# ProDoc.net
KiCad netlist of a schematic drawn in EasyEDA Pro
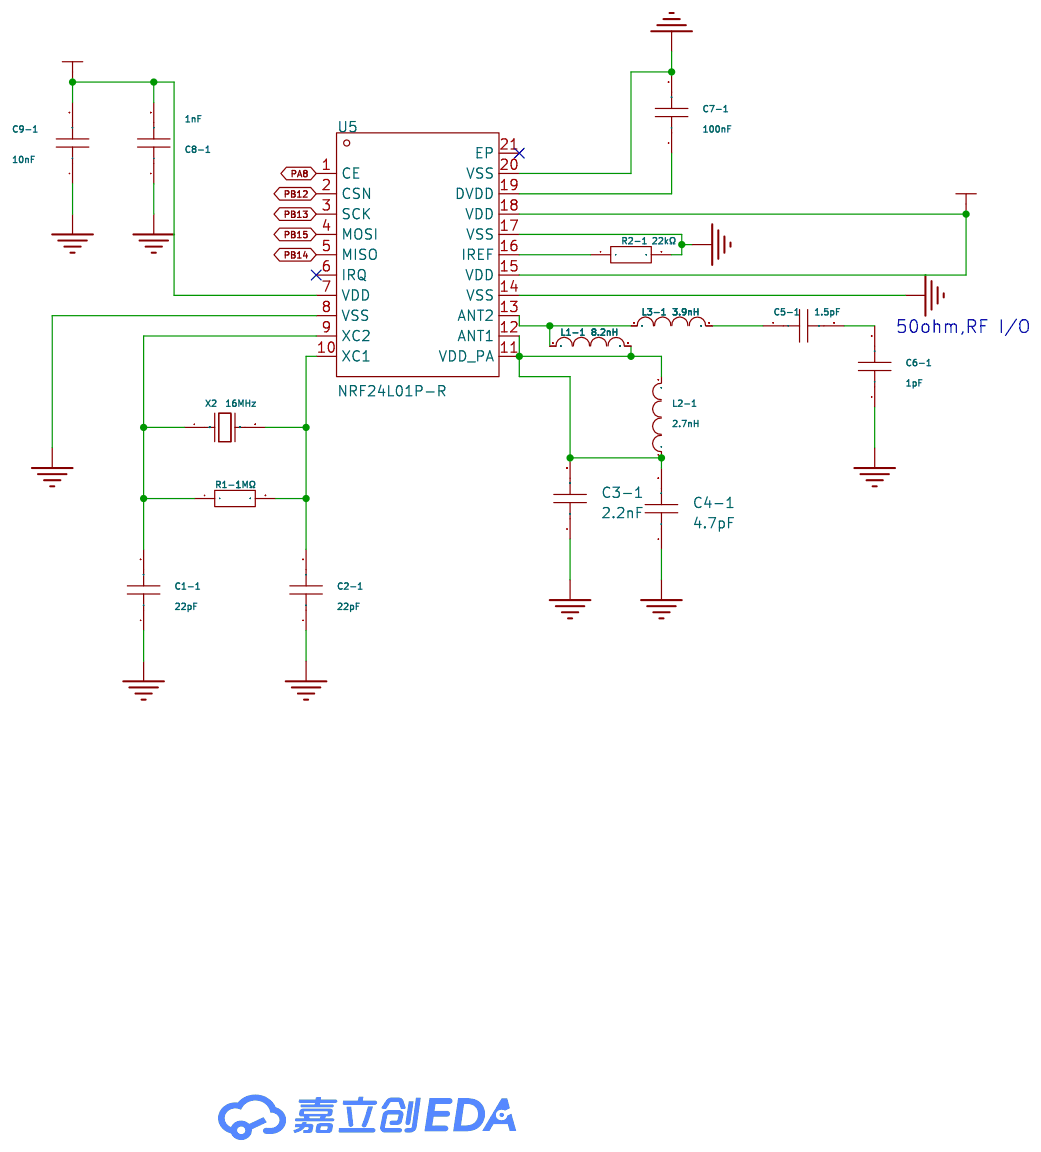
[diagram p0: P2]
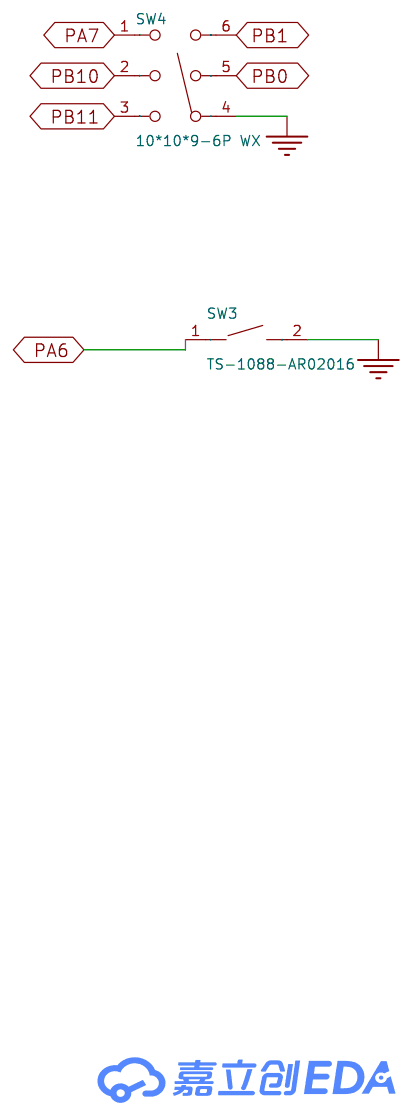
[diagram p1: P3]
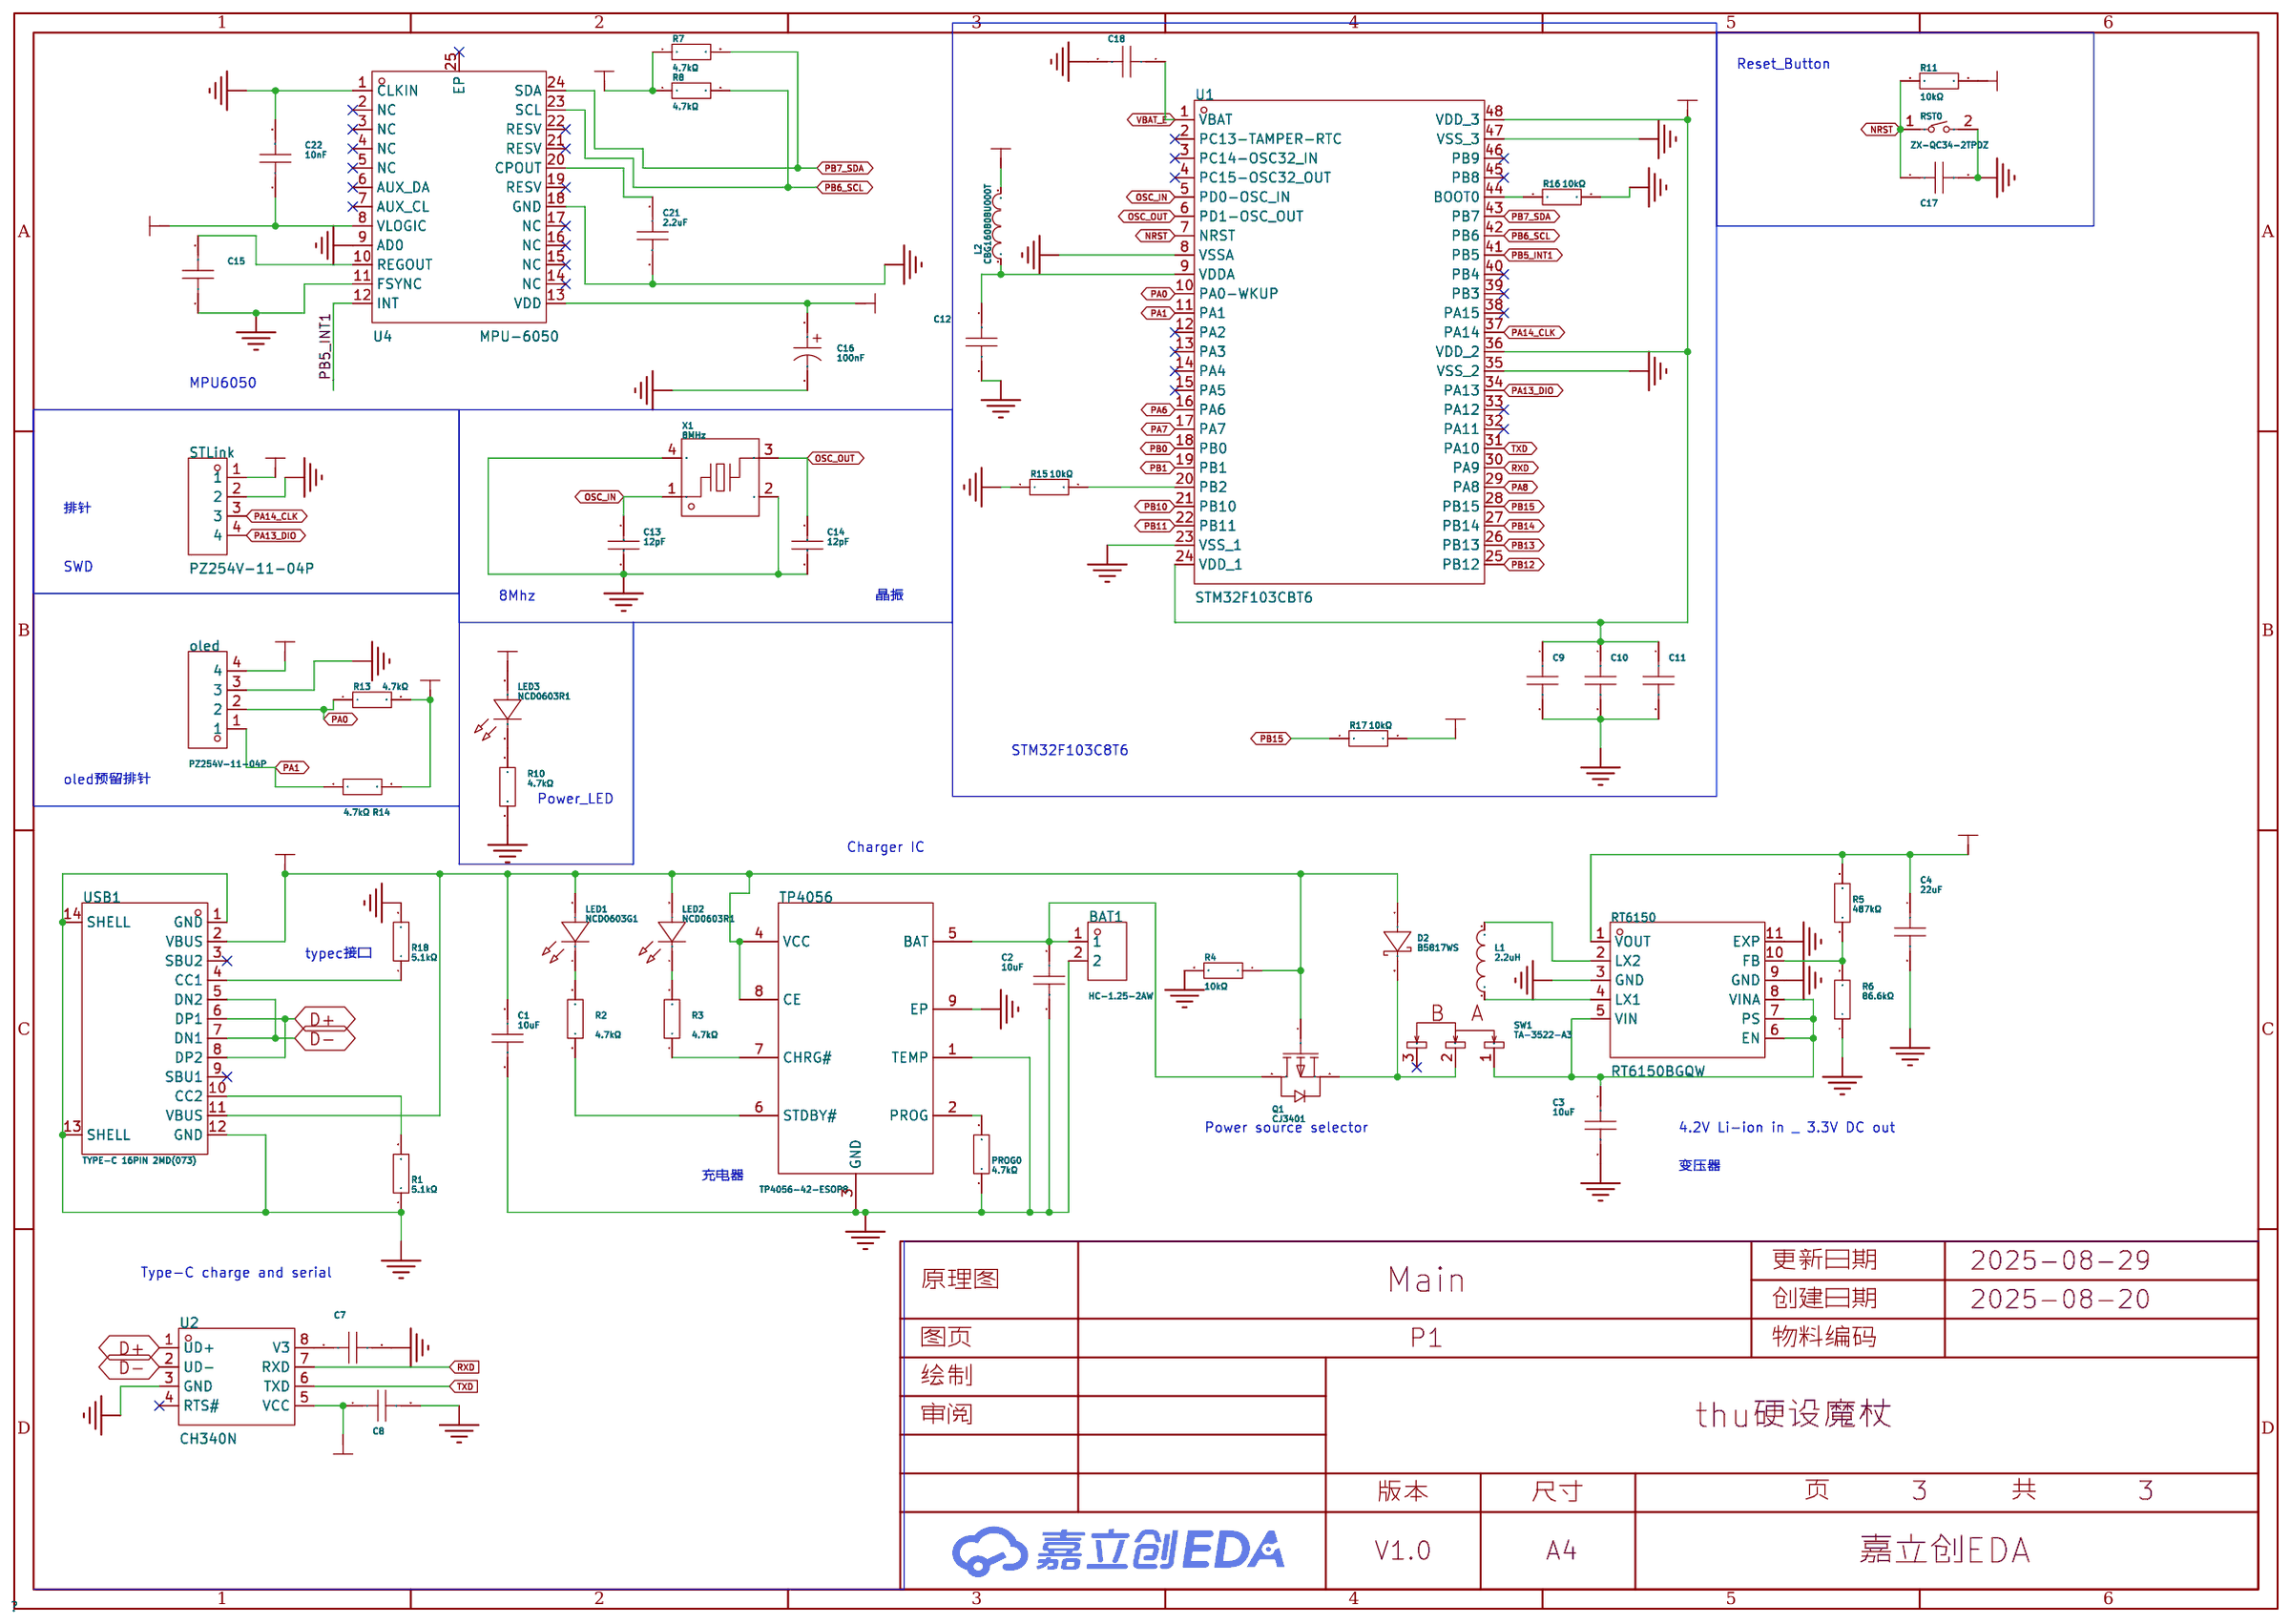
[diagram p2: P1]

(export (version "E")
  (design (tool "Eeschema 10.0.6"))
  (components
    (comp (ref "C1-1")
      (value "22pF")
      (fields
        (field (name "Manufacturer Part") "CL10C220JB8NNNC")
        (field (name "Manufacturer") "SAMSUNG(三星)")
      )
      (libsource (lib "easyedapro") (part "Capacitance"))
    )
    (comp (ref "C2-1")
      (value "22pF")
      (fields
        (field (name "Manufacturer Part") "CL10C220JB8NNNC")
        (field (name "Manufacturer") "SAMSUNG(三星)")
      )
      (libsource (lib "easyedapro") (part "Capacitance"))
    )
    (comp (ref "C3-1")
      (value "2.2nF")
      (fields
        (field (name "Manufacturer Part") "FCC0603B222K500CT")
        (field (name "Manufacturer") "FOJAN(富捷)")
      )
      (libsource (lib "easyedapro") (part "Capacitance"))
    )
    (comp (ref "C4-1")
      (value "4.7pF")
      (fields (field (name "Manufacturer Part") "0603CG4R7C500NT") (field (name "Manufacturer") "FH(风华)"))
      (libsource (lib "easyedapro") (part "Capacitance"))
    )
    (comp (ref "C5-1")
      (value "1.5pF")
      (fields (field (name "Manufacturer Part") "0603CG1R5C500NT") (field (name "Manufacturer") "FH(风华)"))
      (libsource (lib "easyedapro") (part "Capacitance"))
    )
    (comp (ref "C6-1")
      (value "1pF")
      (fields (field (name "Manufacturer Part") "0603CG1R0C500NT") (field (name "Manufacturer") "FH(风华)"))
      (libsource (lib "easyedapro") (part "Capacitance"))
    )
    (comp (ref "C7-1")
      (value "100nF")
      (fields
        (field (name "Manufacturer Part") "CGA0603X7R104K500JT")
        (field (name "Manufacturer") "HRE(芯声)")
      )
      (libsource (lib "easyedapro") (part "Capacitance"))
    )
    (comp (ref "C8-1")
      (value "1nF")
      (fields
        (field (name "Manufacturer Part") "CL10B102KB8NNNC")
        (field (name "Manufacturer") "SAMSUNG(三星)")
      )
      (libsource (lib "easyedapro") (part "Capacitance"))
    )
    (comp (ref "C9-1")
      (value "10nF")
      (fields (field (name "Manufacturer Part") "0603B103K500NT") (field (name "Manufacturer") "FH(风华)"))
      (libsource (lib "easyedapro") (part "Capacitance"))
    )
    (comp (ref "L1-1")
      (value "8.2nH")
      (fields (field (name "Manufacturer Part") "LQG18HN8N2J00D") (field (name "Manufacturer") "muRata(村田)"))
      (libsource (lib "easyedapro") (part "SDFL1608S100KTF"))
    )
    (comp (ref "L2-1")
      (value "2.7nH")
      (fields
        (field (name "Manufacturer Part") "SCC1608C2N7SSP")
        (field (name "Manufacturer") "Sunltech(顺磁)")
      )
      (libsource (lib "easyedapro") (part "SDFL1608S100KTF"))
    )
    (comp (ref "L3-1")
      (value "3.9nH")
      (fields
        (field (name "Manufacturer Part") "SDCL1608C3N9STDF")
        (field (name "Manufacturer") "Sunlord(顺络)")
      )
      (libsource (lib "easyedapro") (part "SDFL1608S100KTF"))
    )
    (comp (ref "R1-1")
      (value "1MΩ")
      (fields
        (field (name "Manufacturer Part") "0603WAF1004T5E")
        (field (name "Manufacturer") "UNI-ROYAL(厚声)")
      )
      (libsource (lib "easyedapro") (part "电阻"))
    )
    (comp (ref "R2-1")
      (value "22kΩ")
      (fields
        (field (name "Manufacturer Part") "0603WAF2202T5E")
        (field (name "Manufacturer") "UNI-ROYAL(厚声)")
      )
      (libsource (lib "easyedapro") (part "电阻"))
    )
    (comp (ref "U5")
      (value "NRF24L01P-R")
      (fields (field (name "Manufacturer") "NORDIC"))
      (libsource (lib "easyedapro") (part "NRF24L01_C1558392"))
    )
    (comp (ref "X2")
      (value "16MHz")
      (fields (field (name "Manufacturer Part") "X49SD16MSD2SC") (field (name "Manufacturer") "YXC(扬兴晶振)"))
      (libsource (lib "easyedapro") (part "SCBYS16X00000ELRJ"))
    )
    (comp (ref "SW3")
      (value "TS-1088-AR02016")
      (footprint "easyedapro:SW-SMD_L3.9-W3.0-P4.45")
      (fields (field (name "Manufacturer") "XUNPU(讯普)"))
      (libsource (lib "easyedapro") (part "TS-1088-AR02016"))
    )
    (comp (ref "SW4")
      (value "10*10*9-6P WX")
      (footprint "easyedapro:SW-SMD-6P-L10.5-W10.0_C2858290")
      (fields (field (name "Manufacturer") "SHOU HAN(首韩)"))
      (libsource (lib "easyedapro") (part "10*10*9-6P WX"))
    )
    (comp (ref "BAT1")
      (value "HC-1.25-2AW")
      (footprint "easyedapro:CONN-TH_2P-P1.25_HCTL_HC-1.25-2AW")
      (fields (field (name "Manufacturer") "HCTL(华灿天禄)"))
      (libsource (lib "easyedapro") (part "HC-1.25-2AW"))
    )
    (comp (ref "C1")
      (value "10uF")
      (fields
        (field (name "Manufacturer Part") "CL10A106KP8NNNC")
        (field (name "Manufacturer") "SAMSUNG(三星)")
      )
      (libsource (lib "easyedapro") (part "CC0603JRNPO9BN101"))
    )
    (comp (ref "C2")
      (value "10uF")
      (fields
        (field (name "Manufacturer Part") "CL10A106KP8NNNC")
        (field (name "Manufacturer") "SAMSUNG(三星)")
      )
      (libsource (lib "easyedapro") (part "CC0603JRNPO9BN101"))
    )
    (comp (ref "C3")
      (value "10uF")
      (fields
        (field (name "Manufacturer Part") "CL10A106KP8NNNC")
        (field (name "Manufacturer") "SAMSUNG(三星)")
      )
      (libsource (lib "easyedapro") (part "CC0603JRNPO9BN101"))
    )
    (comp (ref "C4")
      (value "22uF")
      (fields
        (field (name "Manufacturer Part") "CL10A226MO7JZNC")
        (field (name "Manufacturer") "SAMSUNG(三星)")
      )
      (libsource (lib "easyedapro") (part "CC0603JRNPO9BN101"))
    )
    (comp (ref "C7")
      (value "100nF")
      (fields
        (field (name "Manufacturer Part") "CT41G-0603-2X1-50V-0.1μF-K(N)")
        (field (name "Manufacturer") "TORCH(火炬)")
      )
      (libsource (lib "easyedapro") (part "CC0603JRNPO9BN101"))
    )
    (comp (ref "C8")
      (value "100nF")
      (fields
        (field (name "Manufacturer Part") "CT41G-0603-2X1-50V-0.1μF-K(N)")
        (field (name "Manufacturer") "TORCH(火炬)")
      )
      (libsource (lib "easyedapro") (part "CC0603JRNPO9BN101"))
    )
    (comp (ref "C9")
      (value "100nF")
      (fields
        (field (name "Manufacturer Part") "CT41G-0603-2X1-50V-0.1μF-K(N)")
        (field (name "Manufacturer") "TORCH(火炬)")
      )
      (libsource (lib "easyedapro") (part "CC0603JRNPO9BN101"))
    )
    (comp (ref "C10")
      (value "100nF")
      (fields
        (field (name "Manufacturer Part") "CT41G-0603-2X1-50V-0.1μF-K(N)")
        (field (name "Manufacturer") "TORCH(火炬)")
      )
      (libsource (lib "easyedapro") (part "CC0603JRNPO9BN101"))
    )
    (comp (ref "C11")
      (value "100nF")
      (fields
        (field (name "Manufacturer Part") "CT41G-0603-2X1-50V-0.1μF-K(N)")
        (field (name "Manufacturer") "TORCH(火炬)")
      )
      (libsource (lib "easyedapro") (part "CC0603JRNPO9BN101"))
    )
    (comp (ref "C12")
      (value "100nF")
      (fields
        (field (name "Manufacturer Part") "CT41G-0603-2X1-50V-0.1μF-K(N)")
        (field (name "Manufacturer") "TORCH(火炬)")
      )
      (libsource (lib "easyedapro") (part "CC0603JRNPO9BN101"))
    )
    (comp (ref "C13")
      (value "12pF")
      (fields
        (field (name "Manufacturer Part") "CL10C120JB8NNNC")
        (field (name "Manufacturer") "SAMSUNG(三星)")
      )
      (libsource (lib "easyedapro") (part "CC0603JRNPO9BN200"))
    )
    (comp (ref "C14")
      (value "12pF")
      (fields
        (field (name "Manufacturer Part") "CL10C120JB8NNNC")
        (field (name "Manufacturer") "SAMSUNG(三星)")
      )
      (libsource (lib "easyedapro") (part "CC0603JRNPO9BN200"))
    )
    (comp (ref "C15")
      (value "100nF")
      (fields
        (field (name "Manufacturer Part") "CT41G-0603-2X1-50V-0.1μF-K(N)")
        (field (name "Manufacturer") "TORCH(火炬)")
      )
      (libsource (lib "easyedapro") (part "CC0603JRNPO9BN101"))
    )
    (comp (ref "C16")
      (value "100nF")
      (fields
        (field (name "Manufacturer Part") "CGA0603X7R104K500JT")
        (field (name "Manufacturer") "HRE(芯声)")
      )
      (libsource (lib "easyedapro") (part "CA45-A-35V-0.1UF-K"))
    )
    (comp (ref "C17")
      (value "100nF")
      (fields
        (field (name "Manufacturer Part") "CT41G-0603-2X1-50V-0.1μF-K(N)")
        (field (name "Manufacturer") "TORCH(火炬)")
      )
      (libsource (lib "easyedapro") (part "CC0603JRNPO9BN101"))
    )
    (comp (ref "C18")
      (value "100nF")
      (fields
        (field (name "Manufacturer Part") "CT41G-0603-2X1-50V-0.1μF-K(N)")
        (field (name "Manufacturer") "TORCH(火炬)")
      )
      (libsource (lib "easyedapro") (part "CC0603JRNPO9BN101"))
    )
    (comp (ref "C21")
      (value "2.2uF")
      (fields
        (field (name "Manufacturer Part") "CL10A225KO8NNNC")
        (field (name "Manufacturer") "SAMSUNG(三星)")
      )
      (libsource (lib "easyedapro") (part "CC0603JRNPO9BN101"))
    )
    (comp (ref "C22")
      (value "10nF")
      (fields
        (field (name "Manufacturer Part") "CC0603KRX7R9BB103")
        (field (name "Manufacturer") "YAGEO(国巨)")
      )
      (libsource (lib "easyedapro") (part "CC0603JRNPO9BN101"))
    )
    (comp (ref "D2")
      (value "B5817WS")
      (footprint "easyedapro:SOD-323_L1.7-W1.3-LS2.5-FD")
      (description "二极管配置:独立式;正向压降(Vf):450mV@1.0A;直流反向耐压(Vr):20V;整流电流:1A;")
      (fields (field (name "Manufacturer") "宏嘉诚"))
      (libsource (lib "easyedapro") (part "B5817WS_C7420329"))
    )
    (comp (ref "L1")
      (value "2.2uH")
      (fields (field (name "Manufacturer Part") "CMH160808B2R2MT") (field (name "Manufacturer") "FH(风华)"))
      (libsource (lib "easyedapro") (part "SRN2512-2R2M"))
    )
    (comp (ref "L2")
      (value "CBG160808U000T")
      (footprint "easyedapro:L0603")
      (description "标称阻抗@测试频率:0Ω@100MHz;直流电阻(RDC):100mΩ;")
      (fields (field (name "Manufacturer") "FH(风华)"))
      (libsource (lib "easyedapro") (part "CBG160808U000T"))
    )
    (comp (ref "LED1")
      (value "NCD0603G1")
      (fields (field (name "Manufacturer") "国星光电"))
      (libsource (lib "easyedapro") (part "19-219/GHC-YR2T1B5Y/3T"))
    )
    (comp (ref "LED2")
      (value "NCD0603R1")
      (fields (field (name "Manufacturer") "国星光电"))
      (libsource (lib "easyedapro") (part "XL-1608SURC-06"))
    )
    (comp (ref "LED3")
      (value "NCD0603R1")
      (fields (field (name "Manufacturer") "国星光电"))
      (libsource (lib "easyedapro") (part "XL-1608SURC-06"))
    )
    (comp (ref "oled")
      (value "PZ254V-11-04P")
      (footprint "easyedapro:HDR-TH_4P-P2.54-V-M")
      (fields (field (name "Manufacturer") "XFCN(兴飞)"))
      (libsource (lib "easyedapro") (part "PZ254V-11-04P_C2691448"))
    )
    (comp (ref "PROG0")
      (value "4.7kΩ")
      (footprint "easyedapro:R0603")
      (description "电阻类型:厚膜电阻;阻值:10kΩ;精度:±1%;功率:100mW;最大工作电压:75V;温度系数:±100ppm/°C;")
      (fields
        (field (name "Manufacturer Part") "0603WAF4701T5E")
        (field (name "Manufacturer") "UNI-ROYAL(厚声)")
      )
      (libsource (lib "easyedapro") (part "0603WAF1002T5E"))
    )
    (comp (ref "Q1")
      (value "CJ3401")
      (footprint "easyedapro:SOT-23-3_L2.9-W1.6-P1.90-LS2.8-BR")
      (fields (field (name "Manufacturer") "CJ(江苏长电/长晶)"))
      (libsource (lib "easyedapro") (part "CJ3401"))
    )
    (comp (ref "R1")
      (value "5.1kΩ")
      (footprint "easyedapro:R0603")
      (description "电阻类型:厚膜电阻;阻值:10kΩ;精度:±1%;功率:100mW;最大工作电压:75V;温度系数:±100ppm/°C;")
      (fields
        (field (name "Manufacturer Part") "0603WAF5101T5E")
        (field (name "Manufacturer") "UNI-ROYAL(厚声)")
      )
      (libsource (lib "easyedapro") (part "0603WAF1002T5E"))
    )
    (comp (ref "R2")
      (value "4.7kΩ")
      (footprint "easyedapro:R0603")
      (description "电阻类型:厚膜电阻;阻值:10kΩ;精度:±1%;功率:100mW;最大工作电压:75V;温度系数:±100ppm/°C;")
      (fields
        (field (name "Manufacturer Part") "0603WAF4701T5E")
        (field (name "Manufacturer") "UNI-ROYAL(厚声)")
      )
      (libsource (lib "easyedapro") (part "0603WAF1002T5E"))
    )
    (comp (ref "R3")
      (value "4.7kΩ")
      (footprint "easyedapro:R0603")
      (description "电阻类型:厚膜电阻;阻值:10kΩ;精度:±1%;功率:100mW;最大工作电压:75V;温度系数:±100ppm/°C;")
      (fields
        (field (name "Manufacturer Part") "0603WAF4701T5E")
        (field (name "Manufacturer") "UNI-ROYAL(厚声)")
      )
      (libsource (lib "easyedapro") (part "0603WAF1002T5E"))
    )
    (comp (ref "R4")
      (value "10kΩ")
      (footprint "easyedapro:R0603")
      (description "电阻类型:厚膜电阻;阻值:10kΩ;精度:±1%;功率:100mW;工作电压:75V;温度系数:±100ppm/℃;")
      (fields
        (field (name "Manufacturer Part") "0603WAF1002T5E")
        (field (name "Manufacturer") "UNI-ROYAL(厚声)")
      )
      (libsource (lib "easyedapro") (part "0603WAF1002T5E"))
    )
    (comp (ref "R5")
      (value "487kΩ")
      (footprint "easyedapro:R0603")
      (description "电阻类型:厚膜电阻;阻值:10kΩ;精度:±1%;功率:100mW;最大工作电压:75V;温度系数:±100ppm/°C;")
      (fields (field (name "Manufacturer Part") "ERJ3EKF4873V") (field (name "Manufacturer") "PANASONIC(松下)"))
      (libsource (lib "easyedapro") (part "0603WAF1002T5E"))
    )
    (comp (ref "R6")
      (value "86.6kΩ")
      (footprint "easyedapro:R0603")
      (description "电阻类型:厚膜电阻;阻值:10kΩ;精度:±1%;功率:100mW;最大工作电压:75V;温度系数:±100ppm/°C;")
      (fields (field (name "Manufacturer Part") "RT0603BRD0786K6L") (field (name "Manufacturer") "YAGEO(国巨)"))
      (libsource (lib "easyedapro") (part "0603WAF1002T5E"))
    )
    (comp (ref "R7")
      (value "4.7kΩ")
      (footprint "easyedapro:R0603")
      (description "电阻类型:厚膜电阻;阻值:10kΩ;精度:±1%;功率:100mW;最大工作电压:75V;温度系数:±100ppm/°C;")
      (fields
        (field (name "Manufacturer Part") "0603WAF4701T5E")
        (field (name "Manufacturer") "UNI-ROYAL(厚声)")
      )
      (libsource (lib "easyedapro") (part "0603WAF1002T5E"))
    )
    (comp (ref "R8")
      (value "4.7kΩ")
      (footprint "easyedapro:R0603")
      (description "电阻类型:厚膜电阻;阻值:10kΩ;精度:±1%;功率:100mW;最大工作电压:75V;温度系数:±100ppm/°C;")
      (fields
        (field (name "Manufacturer Part") "0603WAF4701T5E")
        (field (name "Manufacturer") "UNI-ROYAL(厚声)")
      )
      (libsource (lib "easyedapro") (part "0603WAF1002T5E"))
    )
    (comp (ref "R10")
      (value "4.7kΩ")
      (footprint "easyedapro:R0603")
      (description "电阻类型:厚膜电阻;阻值:10kΩ;精度:±1%;功率:100mW;最大工作电压:75V;温度系数:±100ppm/°C;")
      (fields
        (field (name "Manufacturer Part") "0603WAF4701T5E")
        (field (name "Manufacturer") "UNI-ROYAL(厚声)")
      )
      (libsource (lib "easyedapro") (part "0603WAF1002T5E"))
    )
    (comp (ref "R11")
      (value "10kΩ")
      (footprint "easyedapro:R0603")
      (description "电阻类型:厚膜电阻;阻值:10kΩ;精度:±1%;功率:100mW;工作电压:75V;温度系数:±100ppm/℃;")
      (fields
        (field (name "Manufacturer Part") "0603WAF1002T5E")
        (field (name "Manufacturer") "UNI-ROYAL(厚声)")
      )
      (libsource (lib "easyedapro") (part "0603WAF1002T5E"))
    )
    (comp (ref "R13")
      (value "4.7kΩ")
      (fields
        (field (name "Manufacturer Part") "0603WAF4701T5E")
        (field (name "Manufacturer") "UNI-ROYAL(厚声)")
      )
      (libsource (lib "easyedapro") (part "电阻"))
    )
    (comp (ref "R14")
      (value "4.7kΩ")
      (fields
        (field (name "Manufacturer Part") "0603WAF4701T5E")
        (field (name "Manufacturer") "UNI-ROYAL(厚声)")
      )
      (libsource (lib "easyedapro") (part "电阻"))
    )
    (comp (ref "R15")
      (value "10kΩ")
      (description "电阻类型:厚膜电阻;阻值:10kΩ;精度:±1%;功率:100mW;工作电压:75V;温度系数:±100ppm/℃;")
      (fields
        (field (name "Manufacturer Part") "0603WAF1002T5E")
        (field (name "Manufacturer") "UNI-ROYAL(厚声)")
      )
      (libsource (lib "easyedapro") (part "电阻"))
    )
    (comp (ref "R16")
      (value "10kΩ")
      (description "电阻类型:厚膜电阻;阻值:10kΩ;精度:±1%;功率:100mW;工作电压:75V;温度系数:±100ppm/℃;")
      (fields
        (field (name "Manufacturer Part") "0603WAF1002T5E")
        (field (name "Manufacturer") "UNI-ROYAL(厚声)")
      )
      (libsource (lib "easyedapro") (part "电阻"))
    )
    (comp (ref "R17")
      (value "10kΩ")
      (description "电阻类型:厚膜电阻;阻值:10kΩ;精度:±1%;功率:100mW;工作电压:75V;温度系数:±100ppm/℃;")
      (fields
        (field (name "Manufacturer Part") "0603WAF1002T5E")
        (field (name "Manufacturer") "UNI-ROYAL(厚声)")
      )
      (libsource (lib "easyedapro") (part "电阻"))
    )
    (comp (ref "R18")
      (value "5.1kΩ")
      (footprint "easyedapro:R0603")
      (description "电阻类型:厚膜电阻;阻值:10kΩ;精度:±1%;功率:100mW;最大工作电压:75V;温度系数:±100ppm/°C;")
      (fields
        (field (name "Manufacturer Part") "0603WAF5101T5E")
        (field (name "Manufacturer") "UNI-ROYAL(厚声)")
      )
      (libsource (lib "easyedapro") (part "0603WAF1002T5E"))
    )
    (comp (ref "RST0")
      (value "ZX-QC34-2TPDZ")
      (footprint "easyedapro:KEY-SMD_L3.9-W3.0-LS5.0-EH")
      (fields (field (name "Manufacturer") "Megastar(兆星)"))
      (libsource (lib "easyedapro") (part "ZX-QC34-2TPDZ"))
    )
    (comp (ref "RT6150")
      (value "RT6150BGQW")
      (footprint "easyedapro:WSON-10_L2.5-W2.5-P0.50-BL-EP")
      (description "功能类型:升降压型;输入电压:1.8V~5.5V;输出电压:1.8V~5.5V;输出电流(最大值):800mA;")
      (fields (field (name "Manufacturer") "RICHTEK(立锜)"))
      (libsource (lib "easyedapro") (part "RT6150BGQW"))
    )
    (comp (ref "STLink")
      (value "PZ254V-11-04P")
      (footprint "easyedapro:HDR-TH_4P-P2.54-V-M")
      (fields (field (name "Manufacturer") "XFCN(兴飞)"))
      (libsource (lib "easyedapro") (part "PZ254V-11-04P_C2691448"))
    )
    (comp (ref "SW1")
      (value "TA-3522-A3")
      (footprint "easyedapro:SW-TH_3P-L9.1-W3.5-P2.50-A3")
      (fields (field (name "Manufacturer") "Yuandi(元迪)"))
      (libsource (lib "easyedapro") (part "TA-3522-A3"))
    )
    (comp (ref "TP4056")
      (value "TP4056-42-ESOP8")
      (footprint "easyedapro:ESOP-8_L4.9-W3.9-P1.27-LS6.0-BL-EP")
      (description "锂电池充电芯片 42代表电池满电电压4.2V。")
      (fields (field (name "Manufacturer") "TOPPOWER(南京拓微)"))
      (libsource (lib "easyedapro") (part "TP4056"))
    )
    (comp (ref "U1")
      (value "STM32F103CBT6")
      (fields (field (name "Manufacturer") "ST(意法半导体)"))
      (libsource (lib "easyedapro") (part "APM32F103CBT6"))
    )
    (comp (ref "U2")
      (value "CH340N")
      (footprint "easyedapro:SOP-8_L4.9-W3.9-P1.27-LS6.0-BL")
      (fields (field (name "Manufacturer") "WCH(南京沁恒)"))
      (libsource (lib "easyedapro") (part "CH340N_C2977777"))
    )
    (comp (ref "U4")
      (value "MPU-6050")
      (footprint "easyedapro:QFN-24_L4.0-W4.0-P0.50-BL-EP2.7")
      (description "传感器类型:加速度计陀螺仪;")
      (fields (field (name "Manufacturer") "TDK InvenSense(应美盛)"))
      (libsource (lib "easyedapro") (part "MPU-6050_C24112"))
    )
    (comp (ref "USB1")
      (value "TYPE-C 16PIN 2MD(073)")
      (footprint "easyedapro:USB-C-SMD_TYPE-C-6PIN-2MD-073")
      (description "连接器类型:Type-C;标准:-;公母:母;端口数量:1;触点数量:16P;安装方式:卧贴;额定电流 - 电源:5A;工作温度范围:-25°C~+85°C;")
      (fields (field (name "Manufacturer") "SHOU HAN(首韩)"))
      (libsource (lib "easyedapro") (part "TYPE-C 16PIN 2MD(073)"))
    )
    (comp (ref "X1")
      (value "8MHz")
      (fields (field (name "Manufacturer Part") "X32258MOB4SI") (field (name "Manufacturer") "YXC(扬兴晶振)"))
      (libsource (lib "easyedapro") (part "X32258MOB4SI"))
    )
  )
  (nets
    (net (code "1") (name "3V3") (class "Default")
      (node (ref "C10") (pin "1") (pinfunction "1_1") (pintype "unspecified"))
      (node (ref "C11") (pin "1") (pinfunction "1_1") (pintype "unspecified"))
      (node (ref "C16") (pin "1") (pinfunction "1_1") (pintype "input"))
      (node (ref "C22") (pin "1") (pinfunction "1_1") (pintype "unspecified"))
      (node (ref "C4") (pin "1") (pinfunction "1_1") (pintype "unspecified"))
      (node (ref "C8") (pin "1") (pinfunction "1_1") (pintype "unspecified"))
      (node (ref "C8-1") (pin "2") (pinfunction "2_2") (pintype "input"))
      (node (ref "C9") (pin "1") (pinfunction "1_1") (pintype "unspecified"))
      (node (ref "C9-1") (pin "2") (pinfunction "2_2") (pintype "input"))
      (node (ref "L2") (pin "2") (pinfunction "2_2") (pintype "unspecified"))
      (node (ref "LED3") (pin "2") (pinfunction "A_2") (pintype "unspecified"))
      (node (ref "R11") (pin "1") (pinfunction "1_1") (pintype "input"))
      (node (ref "R13") (pin "2") (pinfunction "2_2") (pintype "input"))
      (node (ref "R14") (pin "2") (pinfunction "2_2") (pintype "input"))
      (node (ref "R17") (pin "2") (pinfunction "2_2") (pintype "input"))
      (node (ref "R5") (pin "2") (pinfunction "2_2") (pintype "input"))
      (node (ref "R7") (pin "1") (pinfunction "1_1") (pintype "input"))
      (node (ref "R8") (pin "1") (pinfunction "1_1") (pintype "input"))
      (node (ref "RT6150") (pin "1") (pinfunction "VOUT_1") (pintype "input"))
      (node (ref "STLink") (pin "1") (pinfunction "1_1") (pintype "unspecified"))
      (node (ref "U1") (pin "24") (pinfunction "VDD_1_24") (pintype "unspecified"))
      (node (ref "U1") (pin "36") (pinfunction "VDD_2_36") (pintype "unspecified"))
      (node (ref "U1") (pin "48") (pinfunction "VDD_3_48") (pintype "unspecified"))
      (node (ref "U2") (pin "5") (pinfunction "VCC_5") (pintype "unspecified"))
      (node (ref "U4") (pin "13") (pinfunction "VDD_13") (pintype "unspecified"))
      (node (ref "U4") (pin "8") (pinfunction "VLOGIC_8") (pintype "unspecified"))
      (node (ref "U5") (pin "15") (pinfunction "VDD_15") (pintype "unspecified"))
      (node (ref "U5") (pin "18") (pinfunction "VDD_18") (pintype "unspecified"))
      (node (ref "U5") (pin "7") (pinfunction "VDD_7") (pintype "unspecified"))
      (node (ref "oled") (pin "4") (pinfunction "4_4") (pintype "unspecified"))
    )
    (net (code "2") (name "D+") (class "Default")
      (node (ref "U2") (pin "1") (pinfunction "UD+_1") (pintype "unspecified"))
      (node (ref "USB1") (pin "6") (pinfunction "DP1_6") (pintype "unspecified"))
      (node (ref "USB1") (pin "8") (pinfunction "DP2_8") (pintype "unspecified"))
    )
    (net (code "3") (name "D-") (class "Default")
      (node (ref "U2") (pin "2") (pinfunction "UD-_2") (pintype "unspecified"))
      (node (ref "USB1") (pin "5") (pinfunction "DN2_5") (pintype "unspecified"))
      (node (ref "USB1") (pin "7") (pinfunction "DN1_7") (pintype "unspecified"))
    )
    (net (code "4") (name "GND") (class "Default")
      (node (ref "BAT1") (pin "2") (pinfunction "2_2") (pintype "unspecified"))
      (node (ref "C1") (pin "2") (pinfunction "2_2") (pintype "unspecified"))
      (node (ref "C1-1") (pin "1") (pinfunction "1_1") (pintype "input"))
      (node (ref "C10") (pin "2") (pinfunction "2_2") (pintype "unspecified"))
      (node (ref "C11") (pin "2") (pinfunction "2_2") (pintype "unspecified"))
      (node (ref "C12") (pin "2") (pinfunction "2_2") (pintype "unspecified"))
      (node (ref "C13") (pin "1") (pinfunction "1_1") (pintype "input"))
      (node (ref "C14") (pin "1") (pinfunction "1_1") (pintype "input"))
      (node (ref "C15") (pin "1") (pinfunction "1_1") (pintype "unspecified"))
      (node (ref "C16") (pin "2") (pinfunction "2_2") (pintype "input"))
      (node (ref "C17") (pin "2") (pinfunction "2_2") (pintype "unspecified"))
      (node (ref "C18") (pin "2") (pinfunction "2_2") (pintype "unspecified"))
      (node (ref "C2") (pin "2") (pinfunction "2_2") (pintype "unspecified"))
      (node (ref "C2-1") (pin "1") (pinfunction "1_1") (pintype "input"))
      (node (ref "C21") (pin "2") (pinfunction "2_2") (pintype "unspecified"))
      (node (ref "C22") (pin "2") (pinfunction "2_2") (pintype "unspecified"))
      (node (ref "C3") (pin "2") (pinfunction "2_2") (pintype "unspecified"))
      (node (ref "C3-1") (pin "1") (pinfunction "1_1") (pintype "input"))
      (node (ref "C4") (pin "2") (pinfunction "2_2") (pintype "unspecified"))
      (node (ref "C4-1") (pin "1") (pinfunction "1_1") (pintype "input"))
      (node (ref "C6-1") (pin "1") (pinfunction "1_1") (pintype "input"))
      (node (ref "C7") (pin "2") (pinfunction "2_2") (pintype "unspecified"))
      (node (ref "C7-1") (pin "2") (pinfunction "2_2") (pintype "input"))
      (node (ref "C8") (pin "2") (pinfunction "2_2") (pintype "unspecified"))
      (node (ref "C8-1") (pin "1") (pinfunction "1_1") (pintype "input"))
      (node (ref "C9") (pin "2") (pinfunction "2_2") (pintype "unspecified"))
      (node (ref "C9-1") (pin "1") (pinfunction "1_1") (pintype "input"))
      (node (ref "PROG0") (pin "1") (pinfunction "1_1") (pintype "input"))
      (node (ref "R1") (pin "1") (pinfunction "1_1") (pintype "input"))
      (node (ref "R10") (pin "2") (pinfunction "2_2") (pintype "input"))
      (node (ref "R15") (pin "1") (pinfunction "1_1") (pintype "input"))
      (node (ref "R16") (pin "2") (pinfunction "2_2") (pintype "input"))
      (node (ref "R18") (pin "2") (pinfunction "2_2") (pintype "input"))
      (node (ref "R2-1") (pin "2") (pinfunction "2_2") (pintype "input"))
      (node (ref "R4") (pin "2") (pinfunction "2_2") (pintype "input"))
      (node (ref "R6") (pin "1") (pinfunction "1_1") (pintype "input"))
      (node (ref "RST0") (pin "2") (pinfunction "2_2") (pintype "unspecified"))
      (node (ref "RT6150") (pin "11") (pinfunction "EXP_11") (pintype "input"))
      (node (ref "RT6150") (pin "3") (pinfunction "GND_3") (pintype "input"))
      (node (ref "RT6150") (pin "9") (pinfunction "GND_9") (pintype "input"))
      (node (ref "STLink") (pin "2") (pinfunction "2_2") (pintype "unspecified"))
      (node (ref "SW3") (pin "2") (pinfunction "2_2") (pintype "unspecified"))
      (node (ref "SW4") (pin "4") (pinfunction "4_4") (pintype "unspecified"))
      (node (ref "TP4056") (pin "1") (pinfunction "TEMP_1") (pintype "unspecified"))
      (node (ref "TP4056") (pin "3") (pinfunction "GND_3") (pintype "unspecified"))
      (node (ref "TP4056") (pin "9") (pinfunction "EP_9") (pintype "unspecified"))
      (node (ref "U1") (pin "23") (pinfunction "VSS_1_23") (pintype "unspecified"))
      (node (ref "U1") (pin "35") (pinfunction "VSS_2_35") (pintype "unspecified"))
      (node (ref "U1") (pin "47") (pinfunction "VSS_3_47") (pintype "unspecified"))
      (node (ref "U1") (pin "8") (pinfunction "VSSA_8") (pintype "unspecified"))
      (node (ref "U2") (pin "3") (pinfunction "GND_3") (pintype "unspecified"))
      (node (ref "U4") (pin "1") (pinfunction "CLKIN_1") (pintype "unspecified"))
      (node (ref "U4") (pin "11") (pinfunction "FSYNC_11") (pintype "unspecified"))
      (node (ref "U4") (pin "18") (pinfunction "GND_18") (pintype "unspecified"))
      (node (ref "U4") (pin "9") (pinfunction "AD0_9") (pintype "unspecified"))
      (node (ref "U5") (pin "14") (pinfunction "VSS_14") (pintype "unspecified"))
      (node (ref "U5") (pin "17") (pinfunction "VSS_17") (pintype "unspecified"))
      (node (ref "U5") (pin "20") (pinfunction "VSS_20") (pintype "unspecified"))
      (node (ref "U5") (pin "8") (pinfunction "VSS_8") (pintype "unspecified"))
      (node (ref "USB1") (pin "1") (pinfunction "GND_1") (pintype "unspecified"))
      (node (ref "USB1") (pin "12") (pinfunction "GND_12") (pintype "unspecified"))
      (node (ref "USB1") (pin "13") (pinfunction "SHELL_13") (pintype "unspecified"))
      (node (ref "USB1") (pin "14") (pinfunction "SHELL_14") (pintype "unspecified"))
      (node (ref "X1") (pin "2") (pinfunction "GND_2") (pintype "input"))
      (node (ref "X1") (pin "4") (pinfunction "GND_4") (pintype "input"))
      (node (ref "oled") (pin "3") (pinfunction "3_3") (pintype "unspecified"))
    )
    (net (code "5") (name "NRST") (class "Default")
      (node (ref "C17") (pin "1") (pinfunction "1_1") (pintype "unspecified"))
      (node (ref "R11") (pin "2") (pinfunction "2_2") (pintype "input"))
      (node (ref "RST0") (pin "1") (pinfunction "1_1") (pintype "unspecified"))
      (node (ref "U1") (pin "7") (pinfunction "NRST_7") (pintype "unspecified"))
    )
    (net (code "6") (name "Net-(C5-1-Pad1)") (class "Default")
      (node (ref "C5-1") (pin "1") (pinfunction "1_1") (pintype "input"))
      (node (ref "L3-1") (pin "2") (pinfunction "2_2") (pintype "unspecified"))
    )
    (net (code "7") (name "Net-(C5-1-Pad2)") (class "Default")
      (node (ref "C5-1") (pin "2") (pinfunction "2_2") (pintype "input"))
      (node (ref "C6-1") (pin "2") (pinfunction "2_2") (pintype "input"))
    )
    (net (code "8") (name "Net-(D2-K)") (class "Default")
      (node (ref "D2") (pin "2") (pinfunction "K_2") (pintype "unspecified"))
      (node (ref "Q1") (pin "2") (pinfunction "S_2") (pintype "unspecified"))
      (node (ref "SW1") (pin "2") (pinfunction "2_2") (pintype "unspecified"))
    )
    (net (code "9") (name "Net-(LED1-K)") (class "Default")
      (node (ref "LED1") (pin "1") (pinfunction "K_1") (pintype "unspecified"))
      (node (ref "R2") (pin "2") (pinfunction "2_2") (pintype "input"))
    )
    (net (code "10") (name "Net-(LED2-K)") (class "Default")
      (node (ref "LED2") (pin "1") (pinfunction "K_1") (pintype "unspecified"))
      (node (ref "R3") (pin "2") (pinfunction "2_2") (pintype "input"))
    )
    (net (code "11") (name "Net-(LED3-K)") (class "Default")
      (node (ref "LED3") (pin "1") (pinfunction "K_1") (pintype "unspecified"))
      (node (ref "R10") (pin "1") (pinfunction "1_1") (pintype "input"))
    )
    (net (code "12") (name "Net-(Q1-D)") (class "Default")
      (node (ref "BAT1") (pin "1") (pinfunction "1_1") (pintype "unspecified"))
      (node (ref "C2") (pin "1") (pinfunction "1_1") (pintype "unspecified"))
      (node (ref "Q1") (pin "3") (pinfunction "D_3") (pintype "unspecified"))
      (node (ref "TP4056") (pin "5") (pinfunction "BAT_5") (pintype "unspecified"))
    )
    (net (code "13") (name "Net-(RT6150-EN)") (class "Default")
      (node (ref "C3") (pin "1") (pinfunction "1_1") (pintype "unspecified"))
      (node (ref "RT6150") (pin "5") (pinfunction "VIN_5") (pintype "input"))
      (node (ref "RT6150") (pin "6") (pinfunction "EN_6") (pintype "input"))
      (node (ref "RT6150") (pin "7") (pinfunction "PS_7") (pintype "input"))
      (node (ref "RT6150") (pin "8") (pinfunction "VINA_8") (pintype "input"))
      (node (ref "SW1") (pin "1") (pinfunction "1_1") (pintype "unspecified"))
    )
    (net (code "14") (name "Net-(RT6150-FB)") (class "Default")
      (node (ref "R5") (pin "1") (pinfunction "1_1") (pintype "input"))
      (node (ref "R6") (pin "2") (pinfunction "2_2") (pintype "input"))
      (node (ref "RT6150") (pin "10") (pinfunction "FB_10") (pintype "input"))
    )
    (net (code "15") (name "Net-(RT6150-LX1)") (class "Default")
      (node (ref "L1") (pin "1") (pinfunction "1_1") (pintype "input"))
      (node (ref "RT6150") (pin "4") (pinfunction "LX1_4") (pintype "input"))
    )
    (net (code "16") (name "Net-(RT6150-LX2)") (class "Default")
      (node (ref "L1") (pin "2") (pinfunction "2_2") (pintype "input"))
      (node (ref "RT6150") (pin "2") (pinfunction "LX2_2") (pintype "input"))
    )
    (net (code "17") (name "Net-(TP4056-CHRG#)") (class "Default")
      (node (ref "R3") (pin "1") (pinfunction "1_1") (pintype "input"))
      (node (ref "TP4056") (pin "7") (pinfunction "CHRG#_7") (pintype "unspecified"))
    )
    (net (code "18") (name "Net-(TP4056-PROG)") (class "Default")
      (node (ref "PROG0") (pin "2") (pinfunction "2_2") (pintype "input"))
      (node (ref "TP4056") (pin "2") (pinfunction "PROG_2") (pintype "unspecified"))
    )
    (net (code "19") (name "Net-(TP4056-STDBY#)") (class "Default")
      (node (ref "R2") (pin "1") (pinfunction "1_1") (pintype "input"))
      (node (ref "TP4056") (pin "6") (pinfunction "STDBY#_6") (pintype "unspecified"))
    )
    (net (code "20") (name "Net-(U1-BOOT0)") (class "Default")
      (node (ref "R16") (pin "1") (pinfunction "1_1") (pintype "input"))
      (node (ref "U1") (pin "44") (pinfunction "BOOT0_44") (pintype "unspecified"))
    )
    (net (code "21") (name "Net-(U1-PB2)") (class "Default")
      (node (ref "R15") (pin "2") (pinfunction "2_2") (pintype "input"))
      (node (ref "U1") (pin "20") (pinfunction "PB2_20") (pintype "unspecified"))
    )
    (net (code "22") (name "Net-(U1-VDDA)") (class "Default")
      (node (ref "C12") (pin "1") (pinfunction "1_1") (pintype "unspecified"))
      (node (ref "L2") (pin "1") (pinfunction "1_1") (pintype "unspecified"))
      (node (ref "U1") (pin "9") (pinfunction "VDDA_9") (pintype "unspecified"))
    )
    (net (code "23") (name "Net-(U2-V3)") (class "Default")
      (node (ref "C7") (pin "1") (pinfunction "1_1") (pintype "unspecified"))
      (node (ref "U2") (pin "8") (pinfunction "V3_8") (pintype "unspecified"))
    )
    (net (code "24") (name "Net-(U4-CPOUT)") (class "Default")
      (node (ref "C21") (pin "1") (pinfunction "1_1") (pintype "unspecified"))
      (node (ref "U4") (pin "20") (pinfunction "CPOUT_20") (pintype "unspecified"))
    )
    (net (code "25") (name "Net-(U4-REGOUT)") (class "Default")
      (node (ref "C15") (pin "2") (pinfunction "2_2") (pintype "unspecified"))
      (node (ref "U4") (pin "10") (pinfunction "REGOUT_10") (pintype "unspecified"))
    )
    (net (code "26") (name "Net-(U5-ANT1)") (class "Default")
      (node (ref "C3-1") (pin "2") (pinfunction "2_2") (pintype "input"))
      (node (ref "C4-1") (pin "2") (pinfunction "2_2") (pintype "input"))
      (node (ref "L1-1") (pin "2") (pinfunction "2_2") (pintype "unspecified"))
      (node (ref "L2-1") (pin "1") (pinfunction "1_1") (pintype "unspecified"))
      (node (ref "L2-1") (pin "2") (pinfunction "2_2") (pintype "unspecified"))
      (node (ref "U5") (pin "11") (pinfunction "VDD_PA_11") (pintype "unspecified"))
      (node (ref "U5") (pin "12") (pinfunction "ANT1_12") (pintype "unspecified"))
    )
    (net (code "27") (name "Net-(U5-ANT2)") (class "Default")
      (node (ref "L1-1") (pin "1") (pinfunction "1_1") (pintype "unspecified"))
      (node (ref "L3-1") (pin "1") (pinfunction "1_1") (pintype "unspecified"))
      (node (ref "U5") (pin "13") (pinfunction "ANT2_13") (pintype "unspecified"))
    )
    (net (code "28") (name "Net-(U5-DVDD)") (class "Default")
      (node (ref "C7-1") (pin "1") (pinfunction "1_1") (pintype "input"))
      (node (ref "U5") (pin "19") (pinfunction "DVDD_19") (pintype "unspecified"))
    )
    (net (code "29") (name "Net-(U5-IREF)") (class "Default")
      (node (ref "R2-1") (pin "1") (pinfunction "1_1") (pintype "input"))
      (node (ref "U5") (pin "16") (pinfunction "IREF_16") (pintype "unspecified"))
    )
    (net (code "30") (name "Net-(U5-XC1)") (class "Default")
      (node (ref "C2-1") (pin "2") (pinfunction "2_2") (pintype "input"))
      (node (ref "R1-1") (pin "2") (pinfunction "2_2") (pintype "input"))
      (node (ref "U5") (pin "10") (pinfunction "XC1_10") (pintype "unspecified"))
      (node (ref "X2") (pin "2") (pinfunction "OSC2_2") (pintype "input"))
    )
    (net (code "31") (name "Net-(U5-XC2)") (class "Default")
      (node (ref "C1-1") (pin "2") (pinfunction "2_2") (pintype "input"))
      (node (ref "R1-1") (pin "1") (pinfunction "1_1") (pintype "input"))
      (node (ref "U5") (pin "9") (pinfunction "XC2_9") (pintype "unspecified"))
      (node (ref "X2") (pin "1") (pinfunction "OSC1_1") (pintype "input"))
    )
    (net (code "32") (name "Net-(USB1-CC1)") (class "Default")
      (node (ref "R18") (pin "1") (pinfunction "1_1") (pintype "input"))
      (node (ref "USB1") (pin "4") (pinfunction "CC1_4") (pintype "unspecified"))
    )
    (net (code "33") (name "Net-(USB1-CC2)") (class "Default")
      (node (ref "R1") (pin "2") (pinfunction "2_2") (pintype "input"))
      (node (ref "USB1") (pin "10") (pinfunction "CC2_10") (pintype "unspecified"))
    )
    (net (code "34") (name "OSC_IN") (class "Default")
      (node (ref "C13") (pin "2") (pinfunction "2_2") (pintype "input"))
      (node (ref "U1") (pin "5") (pinfunction "PD0-OSC_IN_5") (pintype "unspecified"))
      (node (ref "X1") (pin "1") (pinfunction "1_1") (pintype "input"))
    )
    (net (code "35") (name "OSC_OUT") (class "Default")
      (node (ref "C14") (pin "2") (pinfunction "2_2") (pintype "input"))
      (node (ref "U1") (pin "6") (pinfunction "PD1-OSC_OUT_6") (pintype "unspecified"))
      (node (ref "X1") (pin "3") (pinfunction "3_3") (pintype "input"))
    )
    (net (code "36") (name "PA0") (class "Default")
      (node (ref "R13") (pin "1") (pinfunction "1_1") (pintype "input"))
      (node (ref "U1") (pin "10") (pinfunction "PA0-WKUP_10") (pintype "unspecified"))
      (node (ref "oled") (pin "2") (pinfunction "2_2") (pintype "unspecified"))
    )
    (net (code "37") (name "PA1") (class "Default")
      (node (ref "R14") (pin "1") (pinfunction "1_1") (pintype "input"))
      (node (ref "U1") (pin "11") (pinfunction "PA1_11") (pintype "unspecified"))
      (node (ref "oled") (pin "1") (pinfunction "1_1") (pintype "unspecified"))
    )
    (net (code "38") (name "PA6") (class "Default")
      (node (ref "SW3") (pin "1") (pinfunction "1_1") (pintype "unspecified"))
      (node (ref "U1") (pin "16") (pinfunction "PA6_16") (pintype "unspecified"))
    )
    (net (code "39") (name "PA7") (class "Default")
      (node (ref "SW4") (pin "1") (pinfunction "1_1") (pintype "unspecified"))
      (node (ref "U1") (pin "17") (pinfunction "PA7_17") (pintype "unspecified"))
    )
    (net (code "40") (name "PA8") (class "Default")
      (node (ref "U1") (pin "29") (pinfunction "PA8_29") (pintype "unspecified"))
      (node (ref "U5") (pin "1") (pinfunction "CE_1") (pintype "unspecified"))
    )
    (net (code "41") (name "PA13_DIO") (class "Default")
      (node (ref "STLink") (pin "4") (pinfunction "4_4") (pintype "unspecified"))
      (node (ref "U1") (pin "34") (pinfunction "PA13_34") (pintype "unspecified"))
    )
    (net (code "42") (name "PA14_CLK") (class "Default")
      (node (ref "STLink") (pin "3") (pinfunction "3_3") (pintype "unspecified"))
      (node (ref "U1") (pin "37") (pinfunction "PA14_37") (pintype "unspecified"))
    )
    (net (code "43") (name "PB0") (class "Default")
      (node (ref "SW4") (pin "5") (pinfunction "5_5") (pintype "unspecified"))
      (node (ref "U1") (pin "18") (pinfunction "PB0_18") (pintype "unspecified"))
    )
    (net (code "44") (name "PB1") (class "Default")
      (node (ref "SW4") (pin "6") (pinfunction "6_6") (pintype "unspecified"))
      (node (ref "U1") (pin "19") (pinfunction "PB1_19") (pintype "unspecified"))
    )
    (net (code "45") (name "PB5_INT1") (class "Default")
      (node (ref "U1") (pin "41") (pinfunction "PB5_41") (pintype "unspecified"))
      (node (ref "U4") (pin "12") (pinfunction "INT_12") (pintype "unspecified"))
    )
    (net (code "46") (name "PB6_SCL") (class "Default")
      (node (ref "R8") (pin "2") (pinfunction "2_2") (pintype "input"))
      (node (ref "U1") (pin "42") (pinfunction "PB6_42") (pintype "unspecified"))
      (node (ref "U4") (pin "23") (pinfunction "SCL_23") (pintype "unspecified"))
    )
    (net (code "47") (name "PB7_SDA") (class "Default")
      (node (ref "R7") (pin "2") (pinfunction "2_2") (pintype "input"))
      (node (ref "U1") (pin "43") (pinfunction "PB7_43") (pintype "unspecified"))
      (node (ref "U4") (pin "24") (pinfunction "SDA_24") (pintype "unspecified"))
    )
    (net (code "48") (name "PB10") (class "Default")
      (node (ref "SW4") (pin "2") (pinfunction "2_2") (pintype "unspecified"))
      (node (ref "U1") (pin "21") (pinfunction "PB10_21") (pintype "unspecified"))
    )
    (net (code "49") (name "PB11") (class "Default")
      (node (ref "SW4") (pin "3") (pinfunction "3_3") (pintype "unspecified"))
      (node (ref "U1") (pin "22") (pinfunction "PB11_22") (pintype "unspecified"))
    )
    (net (code "50") (name "PB12") (class "Default")
      (node (ref "U1") (pin "25") (pinfunction "PB12_25") (pintype "unspecified"))
      (node (ref "U5") (pin "2") (pinfunction "CSN_2") (pintype "unspecified"))
    )
    (net (code "51") (name "PB13") (class "Default")
      (node (ref "U1") (pin "26") (pinfunction "PB13_26") (pintype "unspecified"))
      (node (ref "U5") (pin "3") (pinfunction "SCK_3") (pintype "unspecified"))
    )
    (net (code "52") (name "PB14") (class "Default")
      (node (ref "U1") (pin "27") (pinfunction "PB14_27") (pintype "unspecified"))
      (node (ref "U5") (pin "5") (pinfunction "MISO_5") (pintype "unspecified"))
    )
    (net (code "53") (name "PB15") (class "Default")
      (node (ref "R17") (pin "1") (pinfunction "1_1") (pintype "input"))
      (node (ref "U1") (pin "28") (pinfunction "PB15_28") (pintype "unspecified"))
      (node (ref "U5") (pin "4") (pinfunction "MOSI_4") (pintype "unspecified"))
    )
    (net (code "54") (name "RXD") (class "Default")
      (node (ref "U1") (pin "30") (pinfunction "PA9_30") (pintype "unspecified"))
      (node (ref "U2") (pin "7") (pinfunction "RXD_7") (pintype "unspecified"))
    )
    (net (code "55") (name "TXD") (class "Default")
      (node (ref "U1") (pin "31") (pinfunction "PA10_31") (pintype "unspecified"))
      (node (ref "U2") (pin "6") (pinfunction "TXD_6") (pintype "unspecified"))
    )
    (net (code "56") (name "VBAT_E") (class "Default")
      (node (ref "C18") (pin "1") (pinfunction "1_1") (pintype "unspecified"))
      (node (ref "U1") (pin "1") (pinfunction "VBAT_1") (pintype "unspecified"))
    )
    (net (code "57") (name "VCC_USB") (class "Default")
      (node (ref "C1") (pin "1") (pinfunction "1_1") (pintype "unspecified"))
      (node (ref "D2") (pin "1") (pinfunction "A_1") (pintype "unspecified"))
      (node (ref "LED1") (pin "2") (pinfunction "A_2") (pintype "unspecified"))
      (node (ref "LED2") (pin "2") (pinfunction "A_2") (pintype "unspecified"))
      (node (ref "Q1") (pin "1") (pinfunction "G_1") (pintype "unspecified"))
      (node (ref "R4") (pin "1") (pinfunction "1_1") (pintype "input"))
      (node (ref "TP4056") (pin "4") (pinfunction "VCC_4") (pintype "unspecified"))
      (node (ref "TP4056") (pin "8") (pinfunction "CE_8") (pintype "unspecified"))
      (node (ref "USB1") (pin "11") (pinfunction "VBUS_11") (pintype "unspecified"))
      (node (ref "USB1") (pin "2") (pinfunction "VBUS_2") (pintype "unspecified"))
    )
    (net (code "58") (name "unconnected-(SW1-Pad3)") (class "Default")
      (node (ref "SW1") (pin "3") (pinfunction "3_3") (pintype "unspecified+no_connect"))
    )
    (net (code "59") (name "unconnected-(U1-PA2-Pad12)") (class "Default")
      (node (ref "U1") (pin "12") (pinfunction "PA2_12") (pintype "unspecified+no_connect"))
    )
    (net (code "60") (name "unconnected-(U1-PA3-Pad13)") (class "Default")
      (node (ref "U1") (pin "13") (pinfunction "PA3_13") (pintype "unspecified+no_connect"))
    )
    (net (code "61") (name "unconnected-(U1-PA4-Pad14)") (class "Default")
      (node (ref "U1") (pin "14") (pinfunction "PA4_14") (pintype "unspecified+no_connect"))
    )
    (net (code "62") (name "unconnected-(U1-PA5-Pad15)") (class "Default")
      (node (ref "U1") (pin "15") (pinfunction "PA5_15") (pintype "unspecified+no_connect"))
    )
    (net (code "63") (name "unconnected-(U1-PA11-Pad32)") (class "Default")
      (node (ref "U1") (pin "32") (pinfunction "PA11_32") (pintype "unspecified+no_connect"))
    )
    (net (code "64") (name "unconnected-(U1-PA12-Pad33)") (class "Default")
      (node (ref "U1") (pin "33") (pinfunction "PA12_33") (pintype "unspecified+no_connect"))
    )
    (net (code "65") (name "unconnected-(U1-PA15-Pad38)") (class "Default")
      (node (ref "U1") (pin "38") (pinfunction "PA15_38") (pintype "unspecified+no_connect"))
    )
    (net (code "66") (name "unconnected-(U1-PB3-Pad39)") (class "Default")
      (node (ref "U1") (pin "39") (pinfunction "PB3_39") (pintype "unspecified+no_connect"))
    )
    (net (code "67") (name "unconnected-(U1-PB4-Pad40)") (class "Default")
      (node (ref "U1") (pin "40") (pinfunction "PB4_40") (pintype "unspecified+no_connect"))
    )
    (net (code "68") (name "unconnected-(U1-PB8-Pad45)") (class "Default")
      (node (ref "U1") (pin "45") (pinfunction "PB8_45") (pintype "unspecified+no_connect"))
    )
    (net (code "69") (name "unconnected-(U1-PB9-Pad46)") (class "Default")
      (node (ref "U1") (pin "46") (pinfunction "PB9_46") (pintype "unspecified+no_connect"))
    )
    (net (code "70") (name "unconnected-(U1-PC13-TAMPER-RTC-Pad2)") (class "Default")
      (node (ref "U1") (pin "2") (pinfunction "PC13-TAMPER-RTC_2") (pintype "unspecified+no_connect"))
    )
    (net (code "71") (name "unconnected-(U1-PC14-OSC32_IN-Pad3)") (class "Default")
      (node (ref "U1") (pin "3") (pinfunction "PC14-OSC32_IN_3") (pintype "unspecified+no_connect"))
    )
    (net (code "72") (name "unconnected-(U1-PC15-OSC32_OUT-Pad4)") (class "Default")
      (node (ref "U1") (pin "4") (pinfunction "PC15-OSC32_OUT_4") (pintype "unspecified+no_connect"))
    )
    (net (code "73") (name "unconnected-(U2-RTS#-Pad4)") (class "Default")
      (node (ref "U2") (pin "4") (pinfunction "RTS#_4") (pintype "unspecified+no_connect"))
    )
    (net (code "74") (name "unconnected-(U4-AUX_CL-Pad7)") (class "Default")
      (node (ref "U4") (pin "7") (pinfunction "AUX_CL_7") (pintype "unspecified+no_connect"))
    )
    (net (code "75") (name "unconnected-(U4-AUX_DA-Pad6)") (class "Default")
      (node (ref "U4") (pin "6") (pinfunction "AUX_DA_6") (pintype "unspecified+no_connect"))
    )
    (net (code "76") (name "unconnected-(U4-EP-Pad25)") (class "Default")
      (node (ref "U4") (pin "25") (pinfunction "EP_25") (pintype "unspecified+no_connect"))
    )
    (net (code "77") (name "unconnected-(U4-NC-Pad2)") (class "Default")
      (node (ref "U4") (pin "2") (pinfunction "NC_2") (pintype "unspecified+no_connect"))
    )
    (net (code "78") (name "unconnected-(U4-NC-Pad3)") (class "Default")
      (node (ref "U4") (pin "3") (pinfunction "NC_3") (pintype "unspecified+no_connect"))
    )
    (net (code "79") (name "unconnected-(U4-NC-Pad4)") (class "Default")
      (node (ref "U4") (pin "4") (pinfunction "NC_4") (pintype "unspecified+no_connect"))
    )
    (net (code "80") (name "unconnected-(U4-NC-Pad5)") (class "Default")
      (node (ref "U4") (pin "5") (pinfunction "NC_5") (pintype "unspecified+no_connect"))
    )
    (net (code "81") (name "unconnected-(U4-NC-Pad14)") (class "Default")
      (node (ref "U4") (pin "14") (pinfunction "NC_14") (pintype "unspecified+no_connect"))
    )
    (net (code "82") (name "unconnected-(U4-NC-Pad15)") (class "Default")
      (node (ref "U4") (pin "15") (pinfunction "NC_15") (pintype "unspecified+no_connect"))
    )
    (net (code "83") (name "unconnected-(U4-NC-Pad16)") (class "Default")
      (node (ref "U4") (pin "16") (pinfunction "NC_16") (pintype "unspecified+no_connect"))
    )
    (net (code "84") (name "unconnected-(U4-NC-Pad17)") (class "Default")
      (node (ref "U4") (pin "17") (pinfunction "NC_17") (pintype "unspecified+no_connect"))
    )
    (net (code "85") (name "unconnected-(U4-RESV-Pad19)") (class "Default")
      (node (ref "U4") (pin "19") (pinfunction "RESV_19") (pintype "unspecified+no_connect"))
    )
    (net (code "86") (name "unconnected-(U4-RESV-Pad21)") (class "Default")
      (node (ref "U4") (pin "21") (pinfunction "RESV_21") (pintype "unspecified+no_connect"))
    )
    (net (code "87") (name "unconnected-(U4-RESV-Pad22)") (class "Default")
      (node (ref "U4") (pin "22") (pinfunction "RESV_22") (pintype "unspecified+no_connect"))
    )
    (net (code "88") (name "unconnected-(U5-EP-Pad21)") (class "Default")
      (node (ref "U5") (pin "21") (pinfunction "EP_21") (pintype "unspecified+no_connect"))
    )
    (net (code "89") (name "unconnected-(U5-IRQ-Pad6)") (class "Default")
      (node (ref "U5") (pin "6") (pinfunction "IRQ_6") (pintype "unspecified+no_connect"))
    )
    (net (code "90") (name "unconnected-(USB1-SBU1-Pad9)") (class "Default")
      (node (ref "USB1") (pin "9") (pinfunction "SBU1_9") (pintype "unspecified+no_connect"))
    )
    (net (code "91") (name "unconnected-(USB1-SBU2-Pad3)") (class "Default")
      (node (ref "USB1") (pin "3") (pinfunction "SBU2_3") (pintype "unspecified+no_connect"))
    )
  )
)
